# Photodiode_assembly_v1_1.net
KiCad netlist of a schematic drawn in EAGLE
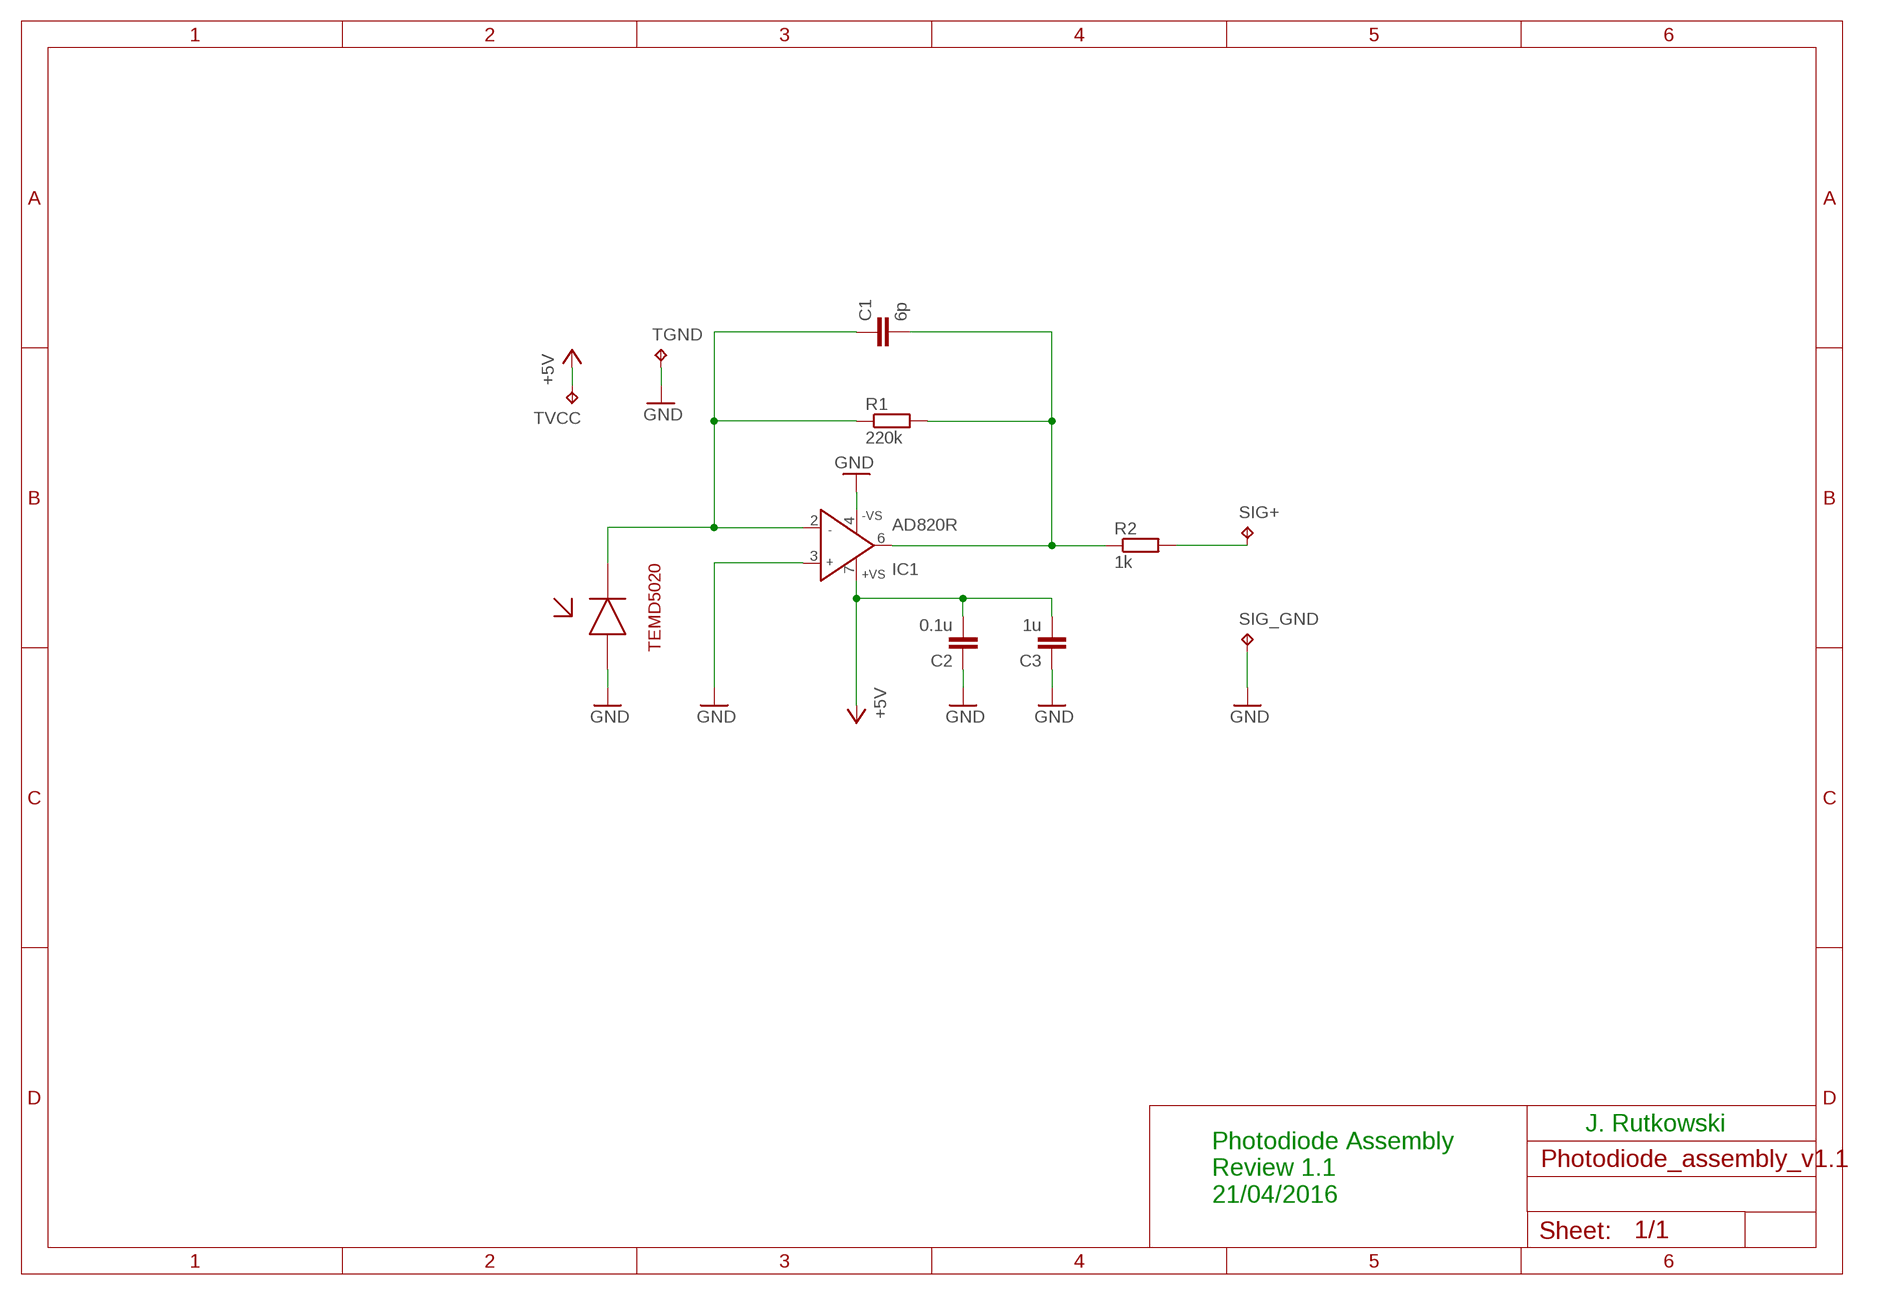
[diagram p0: schematic, sheet 1]

(export (version "E")
  (design (tool "Eeschema 10.0.6"))
  (components
    (comp (ref "C1")
      (value "6p")
      (footprint "eagle-import:C0805K")
      (libsource (lib "eagle-import") (part "C-EUC0805K"))
    )
    (comp (ref "C2")
      (value "0.1u")
      (footprint "eagle-import:C0805K")
      (libsource (lib "eagle-import") (part "C-EUC0805K"))
    )
    (comp (ref "C3")
      (value "1u")
      (footprint "eagle-import:C0805K")
      (libsource (lib "eagle-import") (part "C-EUC0805K"))
    )
    (comp (ref "D1")
      (value "TEMD5020")
      (footprint "eagle-import:TEMD5020_OUTLINE")
      (libsource (lib "eagle-import") (part "TEMD5020"))
    )
    (comp (ref "IC1")
      (value "AD820R")
      (footprint "eagle-import:SO8")
      (libsource (lib "eagle-import") (part "AD820R"))
    )
    (comp (ref "R1")
      (value "220k")
      (footprint "eagle-import:R0805")
      (libsource (lib "eagle-import") (part "R-EU_R0805"))
    )
    (comp (ref "R2")
      (value "1k")
      (footprint "eagle-import:R0805")
      (libsource (lib "eagle-import") (part "R-EU_R0805"))
    )
    (comp (ref "SIG+")
      (value "TPPAD1-13Y")
      (footprint "eagle-import:P1-13Y")
      (libsource (lib "eagle-import") (part "TPPAD1-13Y"))
    )
    (comp (ref "SIG_GND")
      (value "TPPAD1-13Y")
      (footprint "eagle-import:P1-13Y")
      (libsource (lib "eagle-import") (part "TPPAD1-13Y"))
    )
    (comp (ref "TGND")
      (value "TPPAD1-13Y")
      (footprint "eagle-import:P1-13Y")
      (libsource (lib "eagle-import") (part "TPPAD1-13Y"))
    )
    (comp (ref "TVCC")
      (value "TPPAD1-13Y")
      (footprint "eagle-import:P1-13Y")
      (libsource (lib "eagle-import") (part "TPPAD1-13Y"))
    )
  )
  (nets
    (net (code "1") (name "+5V") (class "Default")
      (node (ref "C2") (pin "2") (pinfunction "2_2") (pintype "passive"))
      (node (ref "C3") (pin "2") (pinfunction "2_2") (pintype "passive"))
      (node (ref "IC1") (pin "7") (pinfunction "+VS_7") (pintype "input"))
      (node (ref "TVCC") (pin "TP") (pinfunction "TP_TP") (pintype "input"))
    )
    (net (code "2") (name "GND") (class "Default")
      (node (ref "C2") (pin "1") (pinfunction "1_1") (pintype "passive"))
      (node (ref "C3") (pin "1") (pinfunction "1_1") (pintype "passive"))
      (node (ref "D1") (pin "ANODE_BRD") (pinfunction "ANODE_SYM_ANODE_BRD") (pintype "bidirectional"))
      (node (ref "IC1") (pin "3") (pinfunction "IN+_3") (pintype "input"))
      (node (ref "IC1") (pin "4") (pinfunction "-VS_4") (pintype "input"))
      (node (ref "SIG_GND") (pin "TP") (pinfunction "TP_TP") (pintype "input"))
      (node (ref "TGND") (pin "TP") (pinfunction "TP_TP") (pintype "input"))
    )
    (net (code "3") (name "Net-(D1-CATHODE)") (class "Default")
      (node (ref "C1") (pin "1") (pinfunction "1_1") (pintype "passive"))
      (node (ref "D1") (pin "CATHODE_BRD") (pinfunction "CATHODE_CATHODE_BRD") (pintype "bidirectional"))
      (node (ref "IC1") (pin "2") (pinfunction "IN-_2") (pintype "input"))
      (node (ref "R1") (pin "1") (pinfunction "1_1") (pintype "passive"))
    )
    (net (code "4") (name "Net-(IC1-OUT)") (class "Default")
      (node (ref "C1") (pin "2") (pinfunction "2_2") (pintype "passive"))
      (node (ref "IC1") (pin "6") (pinfunction "OUT_6") (pintype "output"))
      (node (ref "R1") (pin "2") (pinfunction "2_2") (pintype "passive"))
      (node (ref "R2") (pin "1") (pinfunction "1_1") (pintype "passive"))
    )
    (net (code "5") (name "Net-(R2-Pad2)") (class "Default")
      (node (ref "R2") (pin "2") (pinfunction "2_2") (pintype "passive"))
      (node (ref "SIG+") (pin "TP") (pinfunction "TP_TP") (pintype "input"))
    )
  )
)
